# SJH-5XDMount_sch.net
KiCad netlist of a schematic drawn in EAGLE
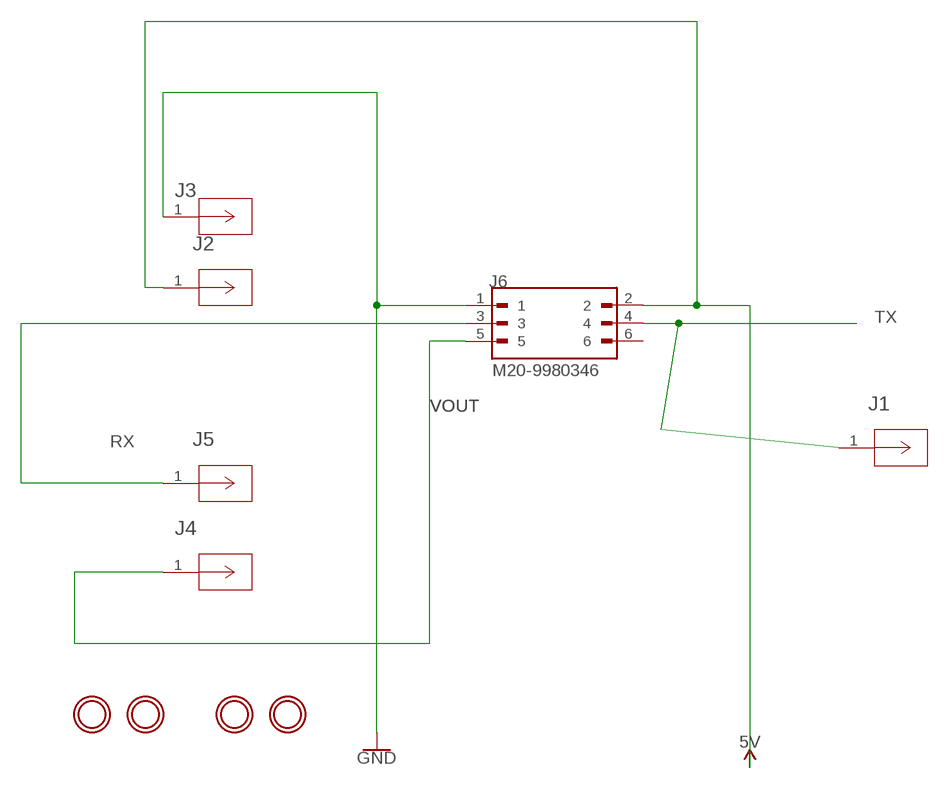
[diagram p0: schematic, sheet 1]

(export (version "E")
  (design (tool "Eeschema 10.0.6"))
  (components
    (comp (ref "J1")
      (value "450-3326-01-03-00")
      (footprint "eagle-import:CONN_450-3326-01-XX-00_CBN")
      (fields (field (name "COPYRIGHT") "Copyright (C) 2024 Ultra Librarian. All rights reserved."))
      (libsource (lib "eagle-import") (part "450-3326-01-03-00"))
    )
    (comp (ref "J2")
      (value "450-3326-01-03-00")
      (footprint "eagle-import:CONN_450-3326-01-XX-00_CBN")
      (fields (field (name "COPYRIGHT") "Copyright (C) 2024 Ultra Librarian. All rights reserved."))
      (libsource (lib "eagle-import") (part "450-3326-01-03-00"))
    )
    (comp (ref "J3")
      (value "450-3326-01-03-00")
      (footprint "eagle-import:CONN_450-3326-01-XX-00_CBN")
      (fields (field (name "COPYRIGHT") "Copyright (C) 2024 Ultra Librarian. All rights reserved."))
      (libsource (lib "eagle-import") (part "450-3326-01-03-00"))
    )
    (comp (ref "J4")
      (value "450-3326-01-03-00")
      (footprint "eagle-import:CONN_450-3326-01-XX-00_CBN")
      (fields (field (name "COPYRIGHT") "Copyright (C) 2024 Ultra Librarian. All rights reserved."))
      (libsource (lib "eagle-import") (part "450-3326-01-03-00"))
    )
    (comp (ref "J5")
      (value "450-3326-01-03-00")
      (footprint "eagle-import:CONN_450-3326-01-XX-00_CBN")
      (fields (field (name "COPYRIGHT") "Copyright (C) 2024 Ultra Librarian. All rights reserved."))
      (libsource (lib "eagle-import") (part "450-3326-01-03-00"))
    )
    (comp (ref "J6")
      (value "M20-9980346")
      (footprint "eagle-import:HARWIN_M20-9980346")
      (fields (field (name "MANUFACTURER") "HARWIN"))
      (libsource (lib "eagle-import") (part "M20-9980346"))
    )
    (comp (ref "U$1")
      (value "MOUNTINGHOLE2.5")
      (footprint "eagle-import:MOUNTINGHOLE_2.5_PLATED")
      (libsource (lib "eagle-import") (part "MOUNTINGHOLE2.5"))
    )
    (comp (ref "U$2")
      (value "MOUNTINGHOLE2.5")
      (footprint "eagle-import:MOUNTINGHOLE_2.5_PLATED")
      (libsource (lib "eagle-import") (part "MOUNTINGHOLE2.5"))
    )
    (comp (ref "U$3")
      (value "MOUNTINGHOLE2.5")
      (footprint "eagle-import:MOUNTINGHOLE_2.5_PLATED")
      (libsource (lib "eagle-import") (part "MOUNTINGHOLE2.5"))
    )
    (comp (ref "U$4")
      (value "MOUNTINGHOLE2.5")
      (footprint "eagle-import:MOUNTINGHOLE_2.5_PLATED")
      (libsource (lib "eagle-import") (part "MOUNTINGHOLE2.5"))
    )
  )
  (nets
    (net (code "1") (name "/RX") (class "Default")
      (node (ref "J5") (pin "1") (pinfunction "1_1") (pintype "passive"))
      (node (ref "J6") (pin "3") (pinfunction "3_3") (pintype "passive"))
    )
    (net (code "2") (name "/TX") (class "Default")
      (node (ref "J1") (pin "1") (pinfunction "1_1") (pintype "passive"))
      (node (ref "J6") (pin "4") (pinfunction "4_4") (pintype "passive"))
    )
    (net (code "3") (name "/VOUT") (class "Default")
      (node (ref "J4") (pin "1") (pinfunction "1_1") (pintype "passive"))
      (node (ref "J6") (pin "5") (pinfunction "5_5") (pintype "passive"))
    )
    (net (code "4") (name "5V") (class "Default")
      (node (ref "J2") (pin "1") (pinfunction "1_1") (pintype "passive"))
      (node (ref "J6") (pin "2") (pinfunction "2_2") (pintype "passive"))
    )
    (net (code "5") (name "GND") (class "Default")
      (node (ref "J3") (pin "1") (pinfunction "1_1") (pintype "passive"))
      (node (ref "J6") (pin "1") (pinfunction "1_1") (pintype "passive"))
    )
    (net (code "6") (name "unconnected-(J6-Pad6)") (class "Default")
      (node (ref "J6") (pin "6") (pinfunction "6_6") (pintype "passive"))
    )
  )
)
